# ET-DAC.net
KiCad netlist of a schematic drawn in Altium Designer
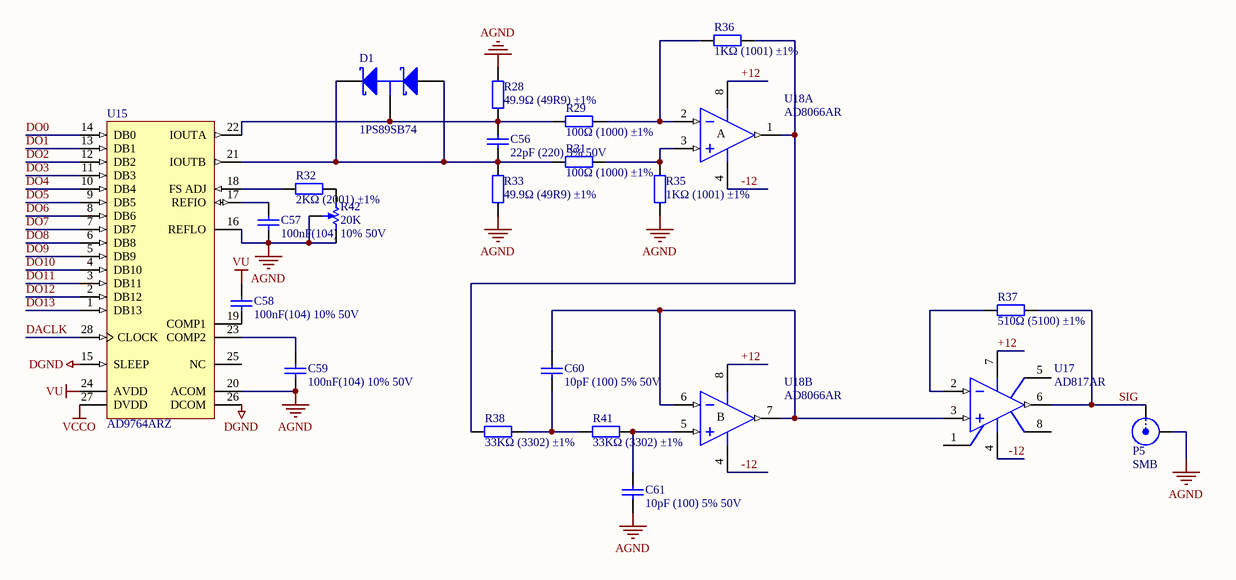
[diagram p0: ET-DAC.SchDoc]

(export (version "E")
  (design (tool "Eeschema 10.0.6"))
  (components
    (comp (ref "C56")
      (value "22pF (220) 5% 50V")
      (footprint "LC-0805_C")
      (description "贴片电容")
      (libsource (lib "Miscellaneous Devices LC") (part "0805 22pF (220) 5% 50V"))
    )
    (comp (ref "C57")
      (value "100nF(104) 10% 50V")
      (footprint "LC-0805_C")
      (description "贴片电容")
      (libsource (lib "Miscellaneous Devices LC") (part "0805 100nF(104) 10% 50V"))
    )
    (comp (ref "C58")
      (value "100nF(104) 10% 50V")
      (footprint "LC-0805_C")
      (description "贴片电容")
      (libsource (lib "Miscellaneous Devices LC") (part "0805 100nF(104) 10% 50V"))
    )
    (comp (ref "C59")
      (value "100nF(104) 10% 50V")
      (footprint "LC-0805_C")
      (description "贴片电容")
      (libsource (lib "Miscellaneous Devices LC") (part "0805 100nF(104) 10% 50V"))
    )
    (comp (ref "C60")
      (value "10pF (100) 5% 50V")
      (footprint "LC-0805_C")
      (description "贴片电容")
      (libsource (lib "Miscellaneous Devices LC") (part "0805 10pF (100) 5% 50V"))
    )
    (comp (ref "C61")
      (value "10pF (100) 5% 50V")
      (footprint "LC-0805_C")
      (description "贴片电容")
      (libsource (lib "Miscellaneous Devices LC") (part "0805 10pF (100) 5% 50V"))
    )
    (comp (ref "D1")
      (value "1PS89SB74")
      (footprint "SOT23_M")
      (description "Schottky Barrier Double Diode")
      (fields (field (name "PUBLISHER") "Altium Limited"))
      (libsource (lib "Philips Discrete Diode - Schottky") (part "1PS89SB74"))
    )
    (comp (ref "P5")
      (value "SMB")
      (footprint "SMB_V-RJ45")
      (description "SMB Straight Connector")
      (fields (field (name "PUBLISHER") "Altium Limited"))
      (libsource (lib "Miscellaneous Connectors") (part "SMB"))
    )
    (comp (ref "R28")
      (value "49.9Ω (49R9) ±1%")
      (footprint "LC-0805_R")
      (description "贴片电阻")
      (libsource (lib "Miscellaneous Devices LC") (part "0805 49.9Ω (49R9) 1%"))
    )
    (comp (ref "R29")
      (value "100Ω (1000) ±1%")
      (footprint "LC-0805_R")
      (description "贴片电阻")
      (libsource (lib "Miscellaneous Devices LC") (part "0805 100Ω (1000) 1%"))
    )
    (comp (ref "R31")
      (value "100Ω (1000) ±1%")
      (footprint "LC-0805_R")
      (description "贴片电阻")
      (libsource (lib "Miscellaneous Devices LC") (part "0805 100Ω (1000) 1%"))
    )
    (comp (ref "R32")
      (value "2KΩ (2001) ±1%")
      (footprint "LC-0805_R")
      (description "贴片电阻")
      (libsource (lib "Miscellaneous Devices LC") (part "0805 2KΩ (2001) 1%"))
    )
    (comp (ref "R33")
      (value "49.9Ω (49R9) ±1%")
      (footprint "LC-0805_R")
      (description "贴片电阻")
      (libsource (lib "Miscellaneous Devices LC") (part "0805 49.9Ω (49R9) 1%"))
    )
    (comp (ref "R35")
      (value "1KΩ (1001) ±1%")
      (footprint "LC-0805_R")
      (description "贴片电阻")
      (libsource (lib "Miscellaneous Devices LC") (part "0805 1KΩ (1001) 1%"))
    )
    (comp (ref "R36")
      (value "1KΩ (1001) ±1%")
      (footprint "LC-0805_R")
      (description "贴片电阻")
      (libsource (lib "") (part "0805 1KΩ (1001) 1%_1"))
    )
    (comp (ref "R37")
      (value "510Ω (5100) ±1%")
      (footprint "LC-0805_R")
      (description "贴片电阻")
      (libsource (lib "Miscellaneous Devices LC") (part "0805 510Ω (5100) 1%"))
    )
    (comp (ref "R38")
      (value "33KΩ (3302) ±1%")
      (footprint "LC-0805_R")
      (description "贴片电阻")
      (libsource (lib "Miscellaneous Devices LC") (part "0805 33KΩ (3302) 1%"))
    )
    (comp (ref "R41")
      (value "33KΩ (3302) ±1%")
      (footprint "LC-0805_R")
      (description "贴片电阻")
      (libsource (lib "Miscellaneous Devices LC") (part "0805 33KΩ (3302) 1%"))
    )
    (comp (ref "R42")
      (value "20K")
      (footprint "POT4MM-2")
      (description "Square Trimming Potentiometer")
      (fields (field (name "PUBLISHER") "Altium Limited"))
      (libsource (lib "Miscellaneous Devices") (part "RPot SM"))
    )
    (comp (ref "U15")
      (value "AD9764ARZ")
      (footprint "mini-ET:RW-28_N")
      (description "Single 14-Bit TxDAC, 125 Msps, -40 to +85 degC, RW-28, Pb-Free, Tube")
      (fields (field (name "GENERIC PART NUMBER") "AD9764") (field (name "MANUFACTURER") "Analog Devices"))
      (libsource (lib "AD Data Converters Digital-to-Analog Converters") (part "AD9764ARZ"))
    )
    (comp (ref "U17")
      (value "AD817AR")
      (footprint "mini-ET:SO-8_N")
      (description "High-Speed, Low-Power Wide Supply Range Amplifier")
      (fields (field (name "PUBLISHER") "Altium Limited"))
      (libsource (lib "AD Operational Amplifier") (part "AD817AR"))
    )
    (comp (ref "U18")
      (value "AD8066AR")
      (footprint "SO-8_N")
      (description "Low Cost, 300MHz Voltage Feedback Amplifier")
      (fields (field (name "PUBLISHER") "Altium Limited"))
      (libsource (lib "AD Operational Amplifier") (part "AD8056AR"))
    )
  )
  (nets
    (net (code "1") (name "/+12") (class "Default")
      (node (ref "U17") (pin "7") (pinfunction "V+_7") (pintype "power_in"))
      (node (ref "U18") (pin "8") (pinfunction "V+_8") (pintype "power_in"))
    )
    (net (code "2") (name "/-12") (class "Default")
      (node (ref "U17") (pin "4") (pinfunction "V-_4") (pintype "power_in"))
      (node (ref "U18") (pin "4") (pinfunction "V-_4") (pintype "power_in"))
    )
    (net (code "3") (name "/DACLK") (class "Default")
      (node (ref "U15") (pin "28") (pinfunction "CLOCK_28") (pintype "input"))
    )
    (net (code "4") (name "/DO0") (class "Default")
      (node (ref "U15") (pin "14") (pinfunction "DB0_14") (pintype "input"))
    )
    (net (code "5") (name "/DO1") (class "Default")
      (node (ref "U15") (pin "13") (pinfunction "DB1_13") (pintype "input"))
    )
    (net (code "6") (name "/DO2") (class "Default")
      (node (ref "U15") (pin "12") (pinfunction "DB2_12") (pintype "input"))
    )
    (net (code "7") (name "/DO3") (class "Default")
      (node (ref "U15") (pin "11") (pinfunction "DB3_11") (pintype "input"))
    )
    (net (code "8") (name "/DO4") (class "Default")
      (node (ref "U15") (pin "10") (pinfunction "DB4_10") (pintype "input"))
    )
    (net (code "9") (name "/DO5") (class "Default")
      (node (ref "U15") (pin "9") (pinfunction "DB5_9") (pintype "input"))
    )
    (net (code "10") (name "/DO6") (class "Default")
      (node (ref "U15") (pin "8") (pinfunction "DB6_8") (pintype "input"))
    )
    (net (code "11") (name "/DO7") (class "Default")
      (node (ref "U15") (pin "7") (pinfunction "DB7_7") (pintype "input"))
    )
    (net (code "12") (name "/DO8") (class "Default")
      (node (ref "U15") (pin "6") (pinfunction "DB8_6") (pintype "input"))
    )
    (net (code "13") (name "/DO9") (class "Default")
      (node (ref "U15") (pin "5") (pinfunction "DB9_5") (pintype "input"))
    )
    (net (code "14") (name "/DO10") (class "Default")
      (node (ref "U15") (pin "4") (pinfunction "DB10_4") (pintype "input"))
    )
    (net (code "15") (name "/DO11") (class "Default")
      (node (ref "U15") (pin "3") (pinfunction "DB11_3") (pintype "input"))
    )
    (net (code "16") (name "/DO12") (class "Default")
      (node (ref "U15") (pin "2") (pinfunction "DB12_2") (pintype "input"))
    )
    (net (code "17") (name "/DO13") (class "Default")
      (node (ref "U15") (pin "1") (pinfunction "DB13_1") (pintype "input"))
    )
    (net (code "18") (name "/SIG") (class "Default")
      (node (ref "P5") (pin "1") (pinfunction "X_1") (pintype "passive"))
      (node (ref "R37") (pin "2") (pinfunction "2_2") (pintype "passive"))
      (node (ref "U17") (pin "6") (pinfunction "OUT_6") (pintype "output"))
    )
    (net (code "19") (name "AGND") (class "Default")
      (node (ref "C57") (pin "1") (pinfunction "1_1") (pintype "passive"))
      (node (ref "C59") (pin "1") (pinfunction "1_1") (pintype "passive"))
      (node (ref "C61") (pin "1") (pinfunction "1_1") (pintype "passive"))
      (node (ref "P5") (pin "2") (pinfunction "Y_2") (pintype "passive"))
      (node (ref "R28") (pin "2") (pinfunction "2_2") (pintype "passive"))
      (node (ref "R33") (pin "1") (pinfunction "1_1") (pintype "passive"))
      (node (ref "R35") (pin "2") (pinfunction "2_2") (pintype "passive"))
      (node (ref "R42") (pin "CW") (pinfunction "+_CW") (pintype "passive"))
      (node (ref "R42") (pin "W") (pinfunction "W_W") (pintype "passive"))
      (node (ref "U15") (pin "16") (pinfunction "REFLO_16") (pintype "passive"))
      (node (ref "U15") (pin "20") (pinfunction "ACOM_20") (pintype "power_in"))
    )
    (net (code "20") (name "DGND") (class "Default")
      (node (ref "U15") (pin "15") (pinfunction "SLEEP_15") (pintype "input"))
      (node (ref "U15") (pin "26") (pinfunction "DCOM_26") (pintype "power_in"))
    )
    (net (code "21") (name "Net-(C60-Pad1)") (class "Default")
      (node (ref "C60") (pin "1") (pinfunction "1_1") (pintype "passive"))
      (node (ref "R38") (pin "2") (pinfunction "2_2") (pintype "passive"))
      (node (ref "R41") (pin "1") (pinfunction "1_1") (pintype "passive"))
    )
    (net (code "22") (name "Net-(D1-A)") (class "Default")
      (node (ref "C56") (pin "1") (pinfunction "1_1") (pintype "passive"))
      (node (ref "D1") (pin "1") (pinfunction "A_1") (pintype "passive"))
      (node (ref "D1") (pin "2") (pinfunction "K_2") (pintype "passive"))
      (node (ref "R31") (pin "1") (pinfunction "1_1") (pintype "passive"))
      (node (ref "R33") (pin "2") (pinfunction "2_2") (pintype "passive"))
      (node (ref "U15") (pin "21") (pinfunction "IOUTB_21") (pintype "output"))
    )
    (net (code "23") (name "Net-(D1-C)") (class "Default")
      (node (ref "C56") (pin "2") (pinfunction "2_2") (pintype "passive"))
      (node (ref "D1") (pin "3") (pinfunction "C_3") (pintype "passive"))
      (node (ref "R28") (pin "1") (pinfunction "1_1") (pintype "passive"))
      (node (ref "R29") (pin "1") (pinfunction "1_1") (pintype "passive"))
      (node (ref "U15") (pin "22") (pinfunction "IOUTA_22") (pintype "output"))
    )
    (net (code "24") (name "Net-(R42--)") (class "Default")
      (node (ref "R32") (pin "1") (pinfunction "1_1") (pintype "passive"))
      (node (ref "R42") (pin "CCW") (pinfunction "-_CCW") (pintype "passive"))
    )
    (net (code "25") (name "Net-(U15-COMP1)") (class "Default")
      (node (ref "C58") (pin "1") (pinfunction "1_1") (pintype "passive"))
      (node (ref "U15") (pin "19") (pinfunction "COMP1_19") (pintype "passive"))
    )
    (net (code "26") (name "Net-(U15-COMP2)") (class "Default")
      (node (ref "C59") (pin "2") (pinfunction "2_2") (pintype "passive"))
      (node (ref "U15") (pin "23") (pinfunction "COMP2_23") (pintype "passive"))
    )
    (net (code "27") (name "Net-(U15-FS_ADJ)") (class "Default")
      (node (ref "R32") (pin "2") (pinfunction "2_2") (pintype "passive"))
      (node (ref "U15") (pin "18") (pinfunction "FS_ADJ_18") (pintype "input"))
    )
    (net (code "28") (name "Net-(U15-REFIO)") (class "Default")
      (node (ref "C57") (pin "2") (pinfunction "2_2") (pintype "passive"))
      (node (ref "U15") (pin "17") (pinfunction "REFIO_17") (pintype "bidirectional"))
    )
    (net (code "29") (name "Net-(U17-IN+)") (class "Default")
      (node (ref "C60") (pin "2") (pinfunction "2_2") (pintype "passive"))
      (node (ref "U17") (pin "3") (pinfunction "IN+_3") (pintype "input"))
      (node (ref "U18") (pin "6") (pinfunction "IN-_6") (pintype "input"))
      (node (ref "U18") (pin "7") (pinfunction "OUT_7") (pintype "output"))
    )
    (net (code "30") (name "Net-(U17-IN-)") (class "Default")
      (node (ref "R37") (pin "1") (pinfunction "1_1") (pintype "passive"))
      (node (ref "U17") (pin "2") (pinfunction "IN-_2") (pintype "input"))
    )
    (net (code "31") (name "Net-(U18A-IN+)") (class "Default")
      (node (ref "R31") (pin "2") (pinfunction "2_2") (pintype "passive"))
      (node (ref "R35") (pin "1") (pinfunction "1_1") (pintype "passive"))
      (node (ref "U18") (pin "3") (pinfunction "IN+_3") (pintype "input"))
    )
    (net (code "32") (name "Net-(U18A-IN-)") (class "Default")
      (node (ref "R29") (pin "2") (pinfunction "2_2") (pintype "passive"))
      (node (ref "R36") (pin "2") (pinfunction "2_2") (pintype "passive"))
      (node (ref "U18") (pin "2") (pinfunction "IN-_2") (pintype "input"))
    )
    (net (code "33") (name "Net-(U18A-OUT)") (class "Default")
      (node (ref "R36") (pin "1") (pinfunction "1_1") (pintype "passive"))
      (node (ref "R38") (pin "1") (pinfunction "1_1") (pintype "passive"))
      (node (ref "U18") (pin "1") (pinfunction "OUT_1") (pintype "output"))
    )
    (net (code "34") (name "Net-(U18B-IN+)") (class "Default")
      (node (ref "C61") (pin "2") (pinfunction "2_2") (pintype "passive"))
      (node (ref "R41") (pin "2") (pinfunction "2_2") (pintype "passive"))
      (node (ref "U18") (pin "5") (pinfunction "IN+_5") (pintype "input"))
    )
    (net (code "35") (name "VCCO") (class "Default")
      (node (ref "U15") (pin "27") (pinfunction "DVDD_27") (pintype "power_in"))
    )
    (net (code "36") (name "VU") (class "Default")
      (node (ref "C58") (pin "2") (pinfunction "2_2") (pintype "passive"))
      (node (ref "U15") (pin "24") (pinfunction "AVDD_24") (pintype "power_in"))
    )
    (net (code "37") (name "unconnected-(U15-NC-Pad25)") (class "Default")
      (node (ref "U15") (pin "25") (pinfunction "NC_25") (pintype "passive"))
    )
    (net (code "38") (name "unconnected-(U17-NC-Pad5)") (class "Default")
      (node (ref "U17") (pin "5") (pinfunction "NC_5") (pintype "passive"))
    )
    (net (code "39") (name "unconnected-(U17-NULL1-Pad1)") (class "Default")
      (node (ref "U17") (pin "1") (pinfunction "NULL1_1") (pintype "passive"))
    )
    (net (code "40") (name "unconnected-(U17-NULL2-Pad8)") (class "Default")
      (node (ref "U17") (pin "8") (pinfunction "NULL2_8") (pintype "passive"))
    )
  )
)
